# Battery_board_V4_1_-_simple_signals.net
KiCad netlist of a schematic drawn in EAGLE
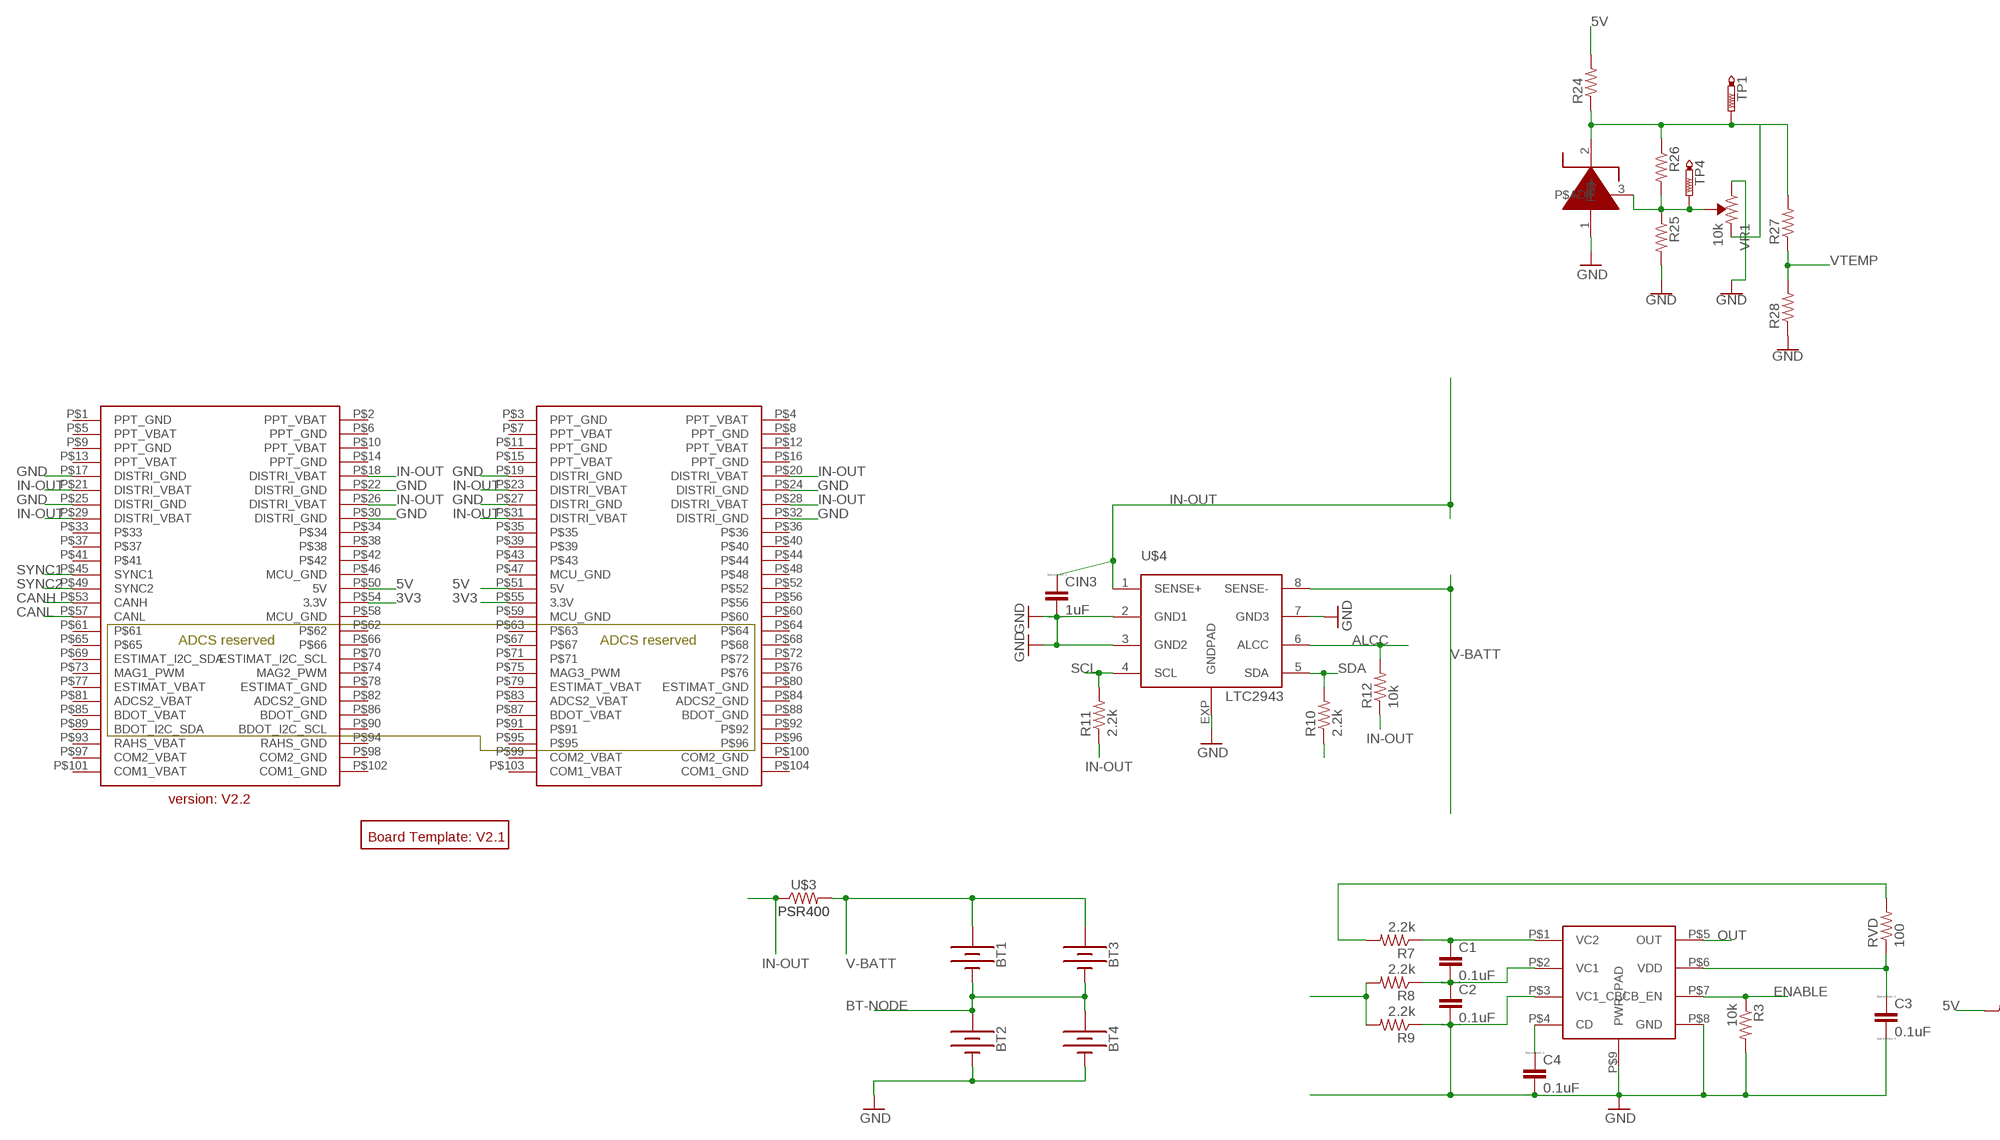
[diagram p0: schematic, sheet 1, part 1 of 2]
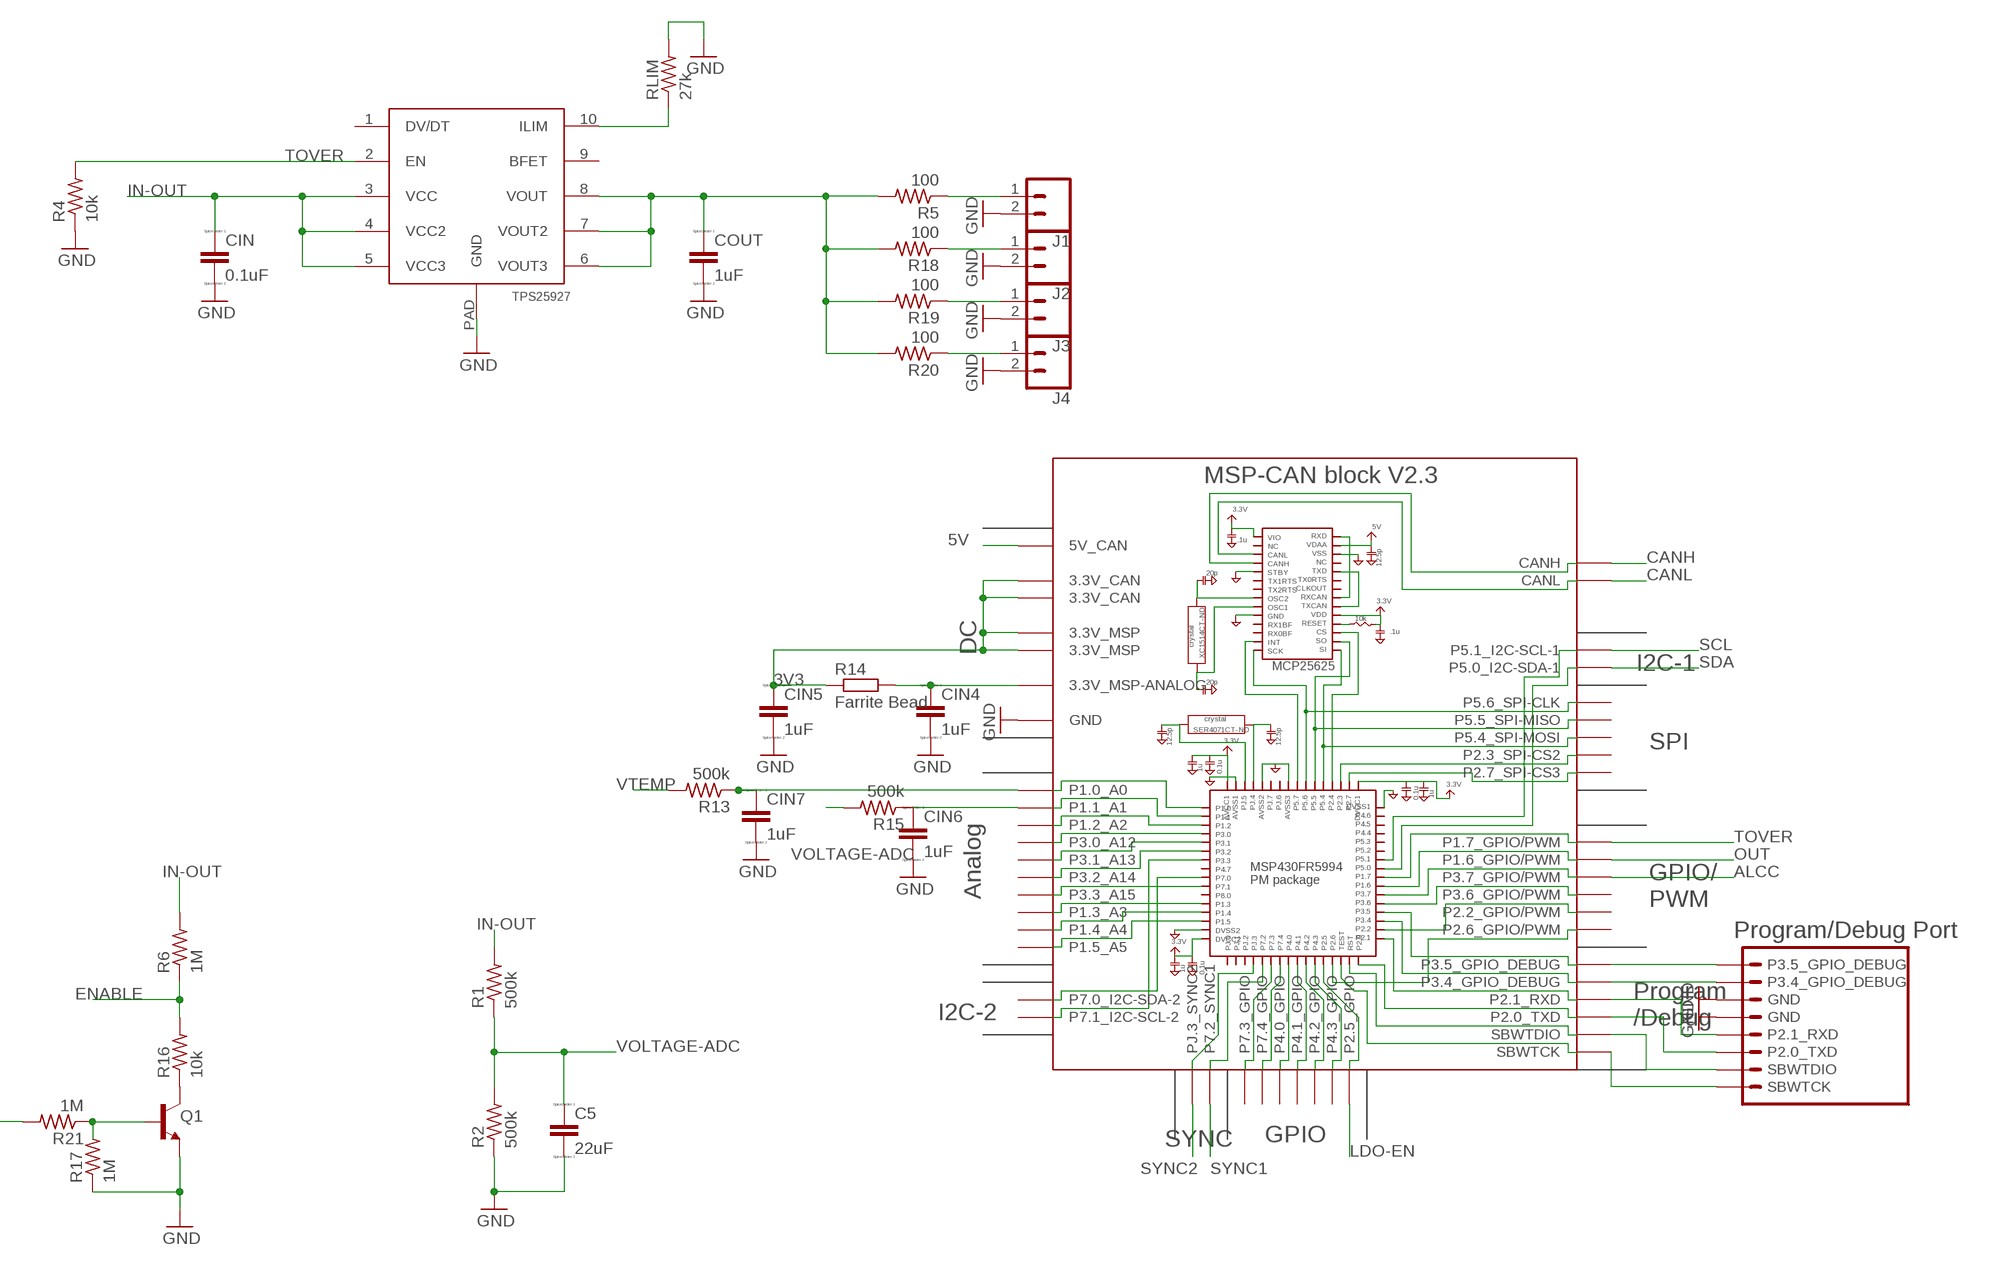
[diagram p1: schematic, sheet 1, part 2 of 2]

(export (version "E")
  (design (tool "Eeschema 10.0.6"))
  (components
    (comp (ref "BT1")
      (value "BATTERY-18650")
      (footprint "eagle-import:BATTERY_18650-HOLDER")
      (libsource (lib "eagle-import") (part "BATTERY-18650"))
    )
    (comp (ref "BT2")
      (value "BATTERY-18650")
      (footprint "eagle-import:BATTERY_18650-HOLDER")
      (libsource (lib "eagle-import") (part "BATTERY-18650"))
    )
    (comp (ref "BT3")
      (value "BATTERY-18650")
      (footprint "eagle-import:BATTERY_18650-HOLDER")
      (libsource (lib "eagle-import") (part "BATTERY-18650"))
    )
    (comp (ref "BT4")
      (value "BATTERY-18650")
      (footprint "eagle-import:BATTERY_18650-HOLDER")
      (libsource (lib "eagle-import") (part "BATTERY-18650"))
    )
    (comp (ref "C1")
      (value "0.1uF")
      (footprint "eagle-import:C0805")
      (libsource (lib "eagle-import") (part "C"))
    )
    (comp (ref "C2")
      (value "0.1uF")
      (footprint "eagle-import:C0805")
      (libsource (lib "eagle-import") (part "C"))
    )
    (comp (ref "C3")
      (value "0.1uF")
      (footprint "eagle-import:C0805")
      (libsource (lib "eagle-import") (part "C"))
    )
    (comp (ref "C4")
      (value "0.1uF")
      (footprint "eagle-import:C0805")
      (libsource (lib "eagle-import") (part "C"))
    )
    (comp (ref "C5")
      (value "22uF")
      (footprint "eagle-import:C1206")
      (libsource (lib "eagle-import") (part "CC1206"))
    )
    (comp (ref "CIN")
      (value "0.1uF")
      (footprint "eagle-import:C0805")
      (libsource (lib "eagle-import") (part "C"))
    )
    (comp (ref "CIN3")
      (value "1uF")
      (footprint "eagle-import:C0805")
      (libsource (lib "eagle-import") (part "C"))
    )
    (comp (ref "CIN4")
      (value "1uF")
      (footprint "eagle-import:C0805")
      (libsource (lib "eagle-import") (part "C"))
    )
    (comp (ref "CIN5")
      (value "1uF")
      (footprint "eagle-import:C0805")
      (libsource (lib "eagle-import") (part "C"))
    )
    (comp (ref "CIN6")
      (value "1uF")
      (footprint "eagle-import:C0805")
      (libsource (lib "eagle-import") (part "C"))
    )
    (comp (ref "CIN7")
      (value "1uF")
      (footprint "eagle-import:C0805")
      (libsource (lib "eagle-import") (part "C"))
    )
    (comp (ref "COUT")
      (value "1uF")
      (footprint "eagle-import:C0805")
      (libsource (lib "eagle-import") (part "C"))
    )
    (comp (ref "J1")
      (value "CONN_02PTH3")
      (footprint "eagle-import:1X02_LONGPADS")
      (libsource (lib "eagle-import") (part "CONN_02PTH3"))
    )
    (comp (ref "J2")
      (value "CONN_02PTH3")
      (footprint "eagle-import:1X02_LONGPADS")
      (libsource (lib "eagle-import") (part "CONN_02PTH3"))
    )
    (comp (ref "J3")
      (value "CONN_02PTH3")
      (footprint "eagle-import:1X02_LONGPADS")
      (libsource (lib "eagle-import") (part "CONN_02PTH3"))
    )
    (comp (ref "J4")
      (value "CONN_02PTH3")
      (footprint "eagle-import:1X02_LONGPADS")
      (libsource (lib "eagle-import") (part "CONN_02PTH3"))
    )
    (comp (ref "Q1")
      (value "TRANS_NPN-MMBT2222AL")
      (footprint "eagle-import:SOT23-3")
      (libsource (lib "eagle-import") (part "TRANS_NPN-MMBT2222AL"))
    )
    (comp (ref "R1")
      (value "500k")
      (footprint "eagle-import:R0805")
      (libsource (lib "eagle-import") (part "R-US_R0805"))
    )
    (comp (ref "R2")
      (value "500k")
      (footprint "eagle-import:R0805")
      (libsource (lib "eagle-import") (part "R-US_R0805"))
    )
    (comp (ref "R3")
      (value "10k")
      (footprint "eagle-import:R0805")
      (libsource (lib "eagle-import") (part "R-US_R0805"))
    )
    (comp (ref "R4")
      (value "10k")
      (footprint "eagle-import:R0805")
      (libsource (lib "eagle-import") (part "R-US_R0805"))
    )
    (comp (ref "R5")
      (value "100")
      (footprint "eagle-import:R0805")
      (libsource (lib "eagle-import") (part "R-US_R0805"))
    )
    (comp (ref "R6")
      (value "1M")
      (footprint "eagle-import:R0805")
      (libsource (lib "eagle-import") (part "R-US_R0805"))
    )
    (comp (ref "R7")
      (value "2.2k")
      (footprint "eagle-import:R0805")
      (libsource (lib "eagle-import") (part "R-US_R0805"))
    )
    (comp (ref "R8")
      (value "2.2k")
      (footprint "eagle-import:R0805")
      (libsource (lib "eagle-import") (part "R-US_R0805"))
    )
    (comp (ref "R9")
      (value "2.2k")
      (footprint "eagle-import:R0805")
      (libsource (lib "eagle-import") (part "R-US_R0805"))
    )
    (comp (ref "R10")
      (value "2.2k")
      (footprint "eagle-import:R0805")
      (libsource (lib "eagle-import") (part "R-US_R0805"))
    )
    (comp (ref "R11")
      (value "2.2k")
      (footprint "eagle-import:R0805")
      (libsource (lib "eagle-import") (part "R-US_R0805"))
    )
    (comp (ref "R12")
      (value "10k")
      (footprint "eagle-import:R0805")
      (libsource (lib "eagle-import") (part "R-US_R0805"))
    )
    (comp (ref "R13")
      (value "500k")
      (footprint "eagle-import:R0805")
      (libsource (lib "eagle-import") (part "R-US_R0805"))
    )
    (comp (ref "R14")
      (value "Farrite Bead")
      (footprint "eagle-import:R1206")
      (libsource (lib "eagle-import") (part "R-EU_R1206"))
    )
    (comp (ref "R15")
      (value "500k")
      (footprint "eagle-import:R0805")
      (libsource (lib "eagle-import") (part "R-US_R0805"))
    )
    (comp (ref "R16")
      (value "10k")
      (footprint "eagle-import:R0805")
      (libsource (lib "eagle-import") (part "R-US_R0805"))
    )
    (comp (ref "R17")
      (value "1M")
      (footprint "eagle-import:M0805")
      (libsource (lib "eagle-import") (part "R-US_M0805"))
    )
    (comp (ref "R18")
      (value "100")
      (footprint "eagle-import:R0805")
      (libsource (lib "eagle-import") (part "R-US_R0805"))
    )
    (comp (ref "R19")
      (value "100")
      (footprint "eagle-import:R0805")
      (libsource (lib "eagle-import") (part "R-US_R0805"))
    )
    (comp (ref "R20")
      (value "100")
      (footprint "eagle-import:R0805")
      (libsource (lib "eagle-import") (part "R-US_R0805"))
    )
    (comp (ref "R21")
      (value "1M")
      (footprint "eagle-import:M0805")
      (libsource (lib "eagle-import") (part "R-US_M0805"))
    )
    (comp (ref "R24")
      (value "R-US_R0805")
      (footprint "eagle-import:R0805")
      (libsource (lib "eagle-import") (part "R-US_R0805"))
    )
    (comp (ref "R25")
      (value "R-US_R0805")
      (footprint "eagle-import:R0805")
      (libsource (lib "eagle-import") (part "R-US_R0805"))
    )
    (comp (ref "R26")
      (value "R-US_R0805")
      (footprint "eagle-import:R0805")
      (libsource (lib "eagle-import") (part "R-US_R0805"))
    )
    (comp (ref "R27")
      (value "R-US_R0805")
      (footprint "eagle-import:R0805")
      (libsource (lib "eagle-import") (part "R-US_R0805"))
    )
    (comp (ref "R28")
      (value "R-US_R0805")
      (footprint "eagle-import:R0805")
      (libsource (lib "eagle-import") (part "R-US_R0805"))
    )
    (comp (ref "RLIM")
      (value "27k")
      (footprint "eagle-import:R0805")
      (libsource (lib "eagle-import") (part "R-US_R0805"))
    )
    (comp (ref "RVD")
      (value "100")
      (footprint "eagle-import:R0805")
      (libsource (lib "eagle-import") (part "R-US_R0805"))
    )
    (comp (ref "TP1")
      (value "PTR1PAD1-13Y")
      (footprint "eagle-import:P1-13Y")
      (libsource (lib "eagle-import") (part "PTR1PAD1-13Y"))
    )
    (comp (ref "TP4")
      (value "PTR1PAD1-13Y")
      (footprint "eagle-import:P1-13Y")
      (libsource (lib "eagle-import") (part "PTR1PAD1-13Y"))
    )
    (comp (ref "U$1")
      (value "MSP-CAN_BLOCK")
      (footprint "eagle-import:MSP-CAN_BLOCK")
      (libsource (lib "eagle-import") (part "MSP-CAN_BLOCK"))
    )
    (comp (ref "U$2")
      (value "PROGRAM/DEBUG_PORT")
      (footprint "eagle-import:1X08_CONNECTOR")
      (libsource (lib "eagle-import") (part "PROGRAM/DEBUG_PORT"))
    )
    (comp (ref "U$3")
      (value "PSR400")
      (footprint "eagle-import:PSR400")
      (libsource (lib "eagle-import") (part "PSR400"))
    )
    (comp (ref "U$4")
      (value "LTC2943")
      (footprint "eagle-import:DFN8(3X3)LT")
      (libsource (lib "eagle-import") (part "LTC2943"))
    )
    (comp (ref "U$5")
      (value "TPS252927")
      (footprint "eagle-import:VSON10")
      (libsource (lib "eagle-import") (part "TPS252927"))
    )
    (comp (ref "U$7")
      (value "2X26_CONNECTOR_(V2.2)")
      (footprint "eagle-import:4X26_CONNECTOR_(V2.2)")
      (libsource (lib "eagle-import") (part "2X26_CONNECTOR_(V2.2)"))
    )
    (comp (ref "U$8")
      (value "BQ29209")
      (footprint "eagle-import:VSON8")
      (libsource (lib "eagle-import") (part "BQ29209"))
    )
    (comp (ref "U$9")
      (value "BOARD_TEMPLATE_(V2.1)")
      (footprint "eagle-import:BOARD_TEMPLATE_(V2.1)")
      (libsource (lib "eagle-import") (part "BOARD_TEMPLATE_(V2.1)"))
    )
    (comp (ref "U$10")
      (value "LM135Z")
      (footprint "eagle-import:TO-92-3")
      (libsource (lib "eagle-import") (part "LM135Z"))
    )
    (comp (ref "VR1")
      (value "10k")
      (footprint "eagle-import:TRIMPOT-SMD-TC33X")
      (libsource (lib "eagle-import") (part "TRIMPOT-SMD-3MM-OPEN-1/10W-25%"))
    )
  )
  (nets
    (net (code "1") (name "/3V3") (class "Default")
      (node (ref "CIN5") (pin "1") (pinfunction "1_1") (pintype "passive"))
      (node (ref "R14") (pin "1") (pinfunction "1_1") (pintype "passive"))
      (node (ref "U$1") (pin "3.3V@CAN1") (pinfunction "3.3V_CAN_3.3V@CAN1") (pintype "bidirectional"))
      (node (ref "U$1") (pin "3.3V@CAN2") (pinfunction "3.3V_CAN_3.3V@CAN2") (pintype "bidirectional"))
      (node (ref "U$1") (pin "3.3V@MSP1") (pinfunction "3.3V_MSP_3.3V@MSP1") (pintype "bidirectional"))
      (node (ref "U$1") (pin "3.3V@MSP2") (pinfunction "3.3V_MSP_3.3V@MSP2") (pintype "bidirectional"))
      (node (ref "U$7") (pin "P$54") (pinfunction "3.3V_P$54") (pintype "bidirectional"))
      (node (ref "U$7") (pin "P$55") (pinfunction "3.3V_P$55") (pintype "bidirectional"))
    )
    (net (code "2") (name "/5V") (class "Default")
      (node (ref "R21") (pin "2") (pinfunction "2_2") (pintype "passive"))
      (node (ref "R24") (pin "2") (pinfunction "2_2") (pintype "passive"))
      (node (ref "U$1") (pin "5V") (pinfunction "5V_CAN_5V") (pintype "bidirectional"))
      (node (ref "U$7") (pin "P$50") (pinfunction "5V_P$50") (pintype "bidirectional"))
      (node (ref "U$7") (pin "P$51") (pinfunction "5V_P$51") (pintype "bidirectional"))
    )
    (net (code "3") (name "/ALCC") (class "Default")
      (node (ref "R12") (pin "2") (pinfunction "2_2") (pintype "passive"))
      (node (ref "U$1") (pin "P3.7_GPIO/PWM") (pinfunction "P3.7_GPIO/PWM_P3.7_GPIO/PWM") (pintype "bidirectional"))
      (node (ref "U$4") (pin "6") (pinfunction "ALCC_6") (pintype "bidirectional"))
    )
    (net (code "4") (name "/BT-NODE") (class "Default")
      (node (ref "BT1") (pin "GND@1") (pinfunction "-_GND@1") (pintype "power_in"))
      (node (ref "BT2") (pin "PWR@1") (pinfunction "+_PWR@1") (pintype "power_in"))
      (node (ref "BT3") (pin "GND@1") (pinfunction "-_GND@1") (pintype "power_in"))
      (node (ref "BT4") (pin "PWR@1") (pinfunction "+_PWR@1") (pintype "power_in"))
      (node (ref "R8") (pin "2") (pinfunction "2_2") (pintype "passive"))
      (node (ref "R9") (pin "2") (pinfunction "2_2") (pintype "passive"))
    )
    (net (code "5") (name "/CANH") (class "Default")
      (node (ref "U$1") (pin "CANH") (pinfunction "CANH_CANH") (pintype "bidirectional"))
      (node (ref "U$7") (pin "P$53") (pinfunction "CANH_P$53") (pintype "bidirectional"))
    )
    (net (code "6") (name "/CANL") (class "Default")
      (node (ref "U$1") (pin "CANL") (pinfunction "CANL_CANL") (pintype "bidirectional"))
      (node (ref "U$7") (pin "P$57") (pinfunction "CANL_P$57") (pintype "bidirectional"))
    )
    (net (code "7") (name "/ENABLE") (class "Default")
      (node (ref "R16") (pin "2") (pinfunction "2_2") (pintype "passive"))
      (node (ref "R3") (pin "1") (pinfunction "1_1") (pintype "passive"))
      (node (ref "R6") (pin "1") (pinfunction "1_1") (pintype "passive"))
      (node (ref "U$8") (pin "P$7") (pinfunction "CB_EN_P$7") (pintype "bidirectional"))
    )
    (net (code "8") (name "/IN-OUT") (class "Default")
      (node (ref "CIN") (pin "1") (pinfunction "1_1") (pintype "passive"))
      (node (ref "CIN3") (pin "1") (pinfunction "1_1") (pintype "passive"))
      (node (ref "R1") (pin "2") (pinfunction "2_2") (pintype "passive"))
      (node (ref "R10") (pin "1") (pinfunction "1_1") (pintype "passive"))
      (node (ref "R11") (pin "1") (pinfunction "1_1") (pintype "passive"))
      (node (ref "R12") (pin "1") (pinfunction "1_1") (pintype "passive"))
      (node (ref "R6") (pin "2") (pinfunction "2_2") (pintype "passive"))
      (node (ref "U$3") (pin "P$1") (pinfunction "1_P$1") (pintype "passive"))
      (node (ref "U$4") (pin "1") (pinfunction "SENSE+_1") (pintype "bidirectional"))
      (node (ref "U$5") (pin "3") (pinfunction "VCC_3") (pintype "bidirectional"))
      (node (ref "U$5") (pin "4") (pinfunction "VCC2_4") (pintype "bidirectional"))
      (node (ref "U$5") (pin "5") (pinfunction "VCC3_5") (pintype "bidirectional"))
      (node (ref "U$7") (pin "P$18") (pinfunction "DISTRI_VBAT_P$18") (pintype "bidirectional"))
      (node (ref "U$7") (pin "P$20") (pinfunction "DISTRI_VBAT_P$20") (pintype "bidirectional"))
      (node (ref "U$7") (pin "P$21") (pinfunction "DISTRI_VBAT_P$21") (pintype "bidirectional"))
      (node (ref "U$7") (pin "P$23") (pinfunction "DISTRI_VBAT_P$23") (pintype "bidirectional"))
      (node (ref "U$7") (pin "P$26") (pinfunction "DISTRI_VBAT_P$26") (pintype "bidirectional"))
      (node (ref "U$7") (pin "P$28") (pinfunction "DISTRI_VBAT_P$28") (pintype "bidirectional"))
      (node (ref "U$7") (pin "P$29") (pinfunction "DISTRI_VBAT_P$29") (pintype "bidirectional"))
      (node (ref "U$7") (pin "P$31") (pinfunction "DISTRI_VBAT_P$31") (pintype "bidirectional"))
    )
    (net (code "9") (name "/LDO-EN") (class "Default")
      (node (ref "U$1") (pin "P2.5_GPIO") (pinfunction "P2.5_GPIO_P2.5_GPIO") (pintype "bidirectional"))
    )
    (net (code "10") (name "/OUT") (class "Default")
      (node (ref "U$1") (pin "P1.6_GPIO/PWM") (pinfunction "P1.6_GPIO/PWM_P1.6_GPIO/PWM") (pintype "bidirectional"))
      (node (ref "U$8") (pin "P$5") (pinfunction "OUT_P$5") (pintype "bidirectional"))
    )
    (net (code "11") (name "/SCL") (class "Default")
      (node (ref "R11") (pin "2") (pinfunction "2_2") (pintype "passive"))
      (node (ref "U$1") (pin "P5.1_I2C-SCL-1") (pinfunction "P5.1_I2C-SCL-1_P5.1_I2C-SCL-1") (pintype "bidirectional"))
      (node (ref "U$4") (pin "4") (pinfunction "SCL_4") (pintype "bidirectional"))
    )
    (net (code "12") (name "/SDA") (class "Default")
      (node (ref "R10") (pin "2") (pinfunction "2_2") (pintype "passive"))
      (node (ref "U$1") (pin "P5.0_I2C-SDA-1") (pinfunction "P5.0_I2C-SDA-1_P5.0_I2C-SDA-1") (pintype "bidirectional"))
      (node (ref "U$4") (pin "5") (pinfunction "SDA_5") (pintype "bidirectional"))
    )
    (net (code "13") (name "/SYNC1") (class "Default")
      (node (ref "U$1") (pin "P7.2_SYNC1") (pinfunction "P7.2_SYNC1_P7.2_SYNC1") (pintype "bidirectional"))
      (node (ref "U$7") (pin "P$45") (pinfunction "SYNC1_P$45") (pintype "bidirectional"))
    )
    (net (code "14") (name "/SYNC2") (class "Default")
      (node (ref "U$1") (pin "PJ.3_SYNC2") (pinfunction "PJ.3_SYNC2_PJ.3_SYNC2") (pintype "bidirectional"))
      (node (ref "U$7") (pin "P$49") (pinfunction "SYNC2_P$49") (pintype "bidirectional"))
    )
    (net (code "15") (name "/TOVER") (class "Default")
      (node (ref "R4") (pin "2") (pinfunction "2_2") (pintype "passive"))
      (node (ref "U$1") (pin "P1.7_GPIO/PWM") (pinfunction "P1.7_GPIO/PWM_P1.7_GPIO/PWM") (pintype "bidirectional"))
      (node (ref "U$5") (pin "2") (pinfunction "EN_2") (pintype "bidirectional"))
    )
    (net (code "16") (name "/V-BATT") (class "Default")
      (node (ref "BT1") (pin "PWR@1") (pinfunction "+_PWR@1") (pintype "power_in"))
      (node (ref "BT3") (pin "PWR@1") (pinfunction "+_PWR@1") (pintype "power_in"))
      (node (ref "R7") (pin "2") (pinfunction "2_2") (pintype "passive"))
      (node (ref "RVD") (pin "2") (pinfunction "2_2") (pintype "passive"))
      (node (ref "U$3") (pin "P$2") (pinfunction "2_P$2") (pintype "passive"))
      (node (ref "U$4") (pin "8") (pinfunction "SENSE-_8") (pintype "bidirectional"))
    )
    (net (code "17") (name "/VOLTAGE-ADC") (class "Default")
      (node (ref "C5") (pin "1") (pinfunction "1_1") (pintype "passive"))
      (node (ref "R1") (pin "1") (pinfunction "1_1") (pintype "passive"))
      (node (ref "R15") (pin "2") (pinfunction "2_2") (pintype "passive"))
      (node (ref "R2") (pin "2") (pinfunction "2_2") (pintype "passive"))
    )
    (net (code "18") (name "/VTEMP") (class "Default")
      (node (ref "R13") (pin "2") (pinfunction "2_2") (pintype "passive"))
      (node (ref "R27") (pin "1") (pinfunction "1_1") (pintype "passive"))
      (node (ref "R28") (pin "2") (pinfunction "2_2") (pintype "passive"))
    )
    (net (code "19") (name "GND") (class "Default")
      (node (ref "BT2") (pin "GND@1") (pinfunction "-_GND@1") (pintype "power_in"))
      (node (ref "BT4") (pin "GND@1") (pinfunction "-_GND@1") (pintype "power_in"))
      (node (ref "C2") (pin "2") (pinfunction "2_2") (pintype "passive"))
      (node (ref "C3") (pin "2") (pinfunction "2_2") (pintype "passive"))
      (node (ref "C4") (pin "2") (pinfunction "2_2") (pintype "passive"))
      (node (ref "C5") (pin "2") (pinfunction "2_2") (pintype "passive"))
      (node (ref "CIN") (pin "2") (pinfunction "2_2") (pintype "passive"))
      (node (ref "CIN3") (pin "2") (pinfunction "2_2") (pintype "passive"))
      (node (ref "CIN4") (pin "2") (pinfunction "2_2") (pintype "passive"))
      (node (ref "CIN5") (pin "2") (pinfunction "2_2") (pintype "passive"))
      (node (ref "CIN6") (pin "2") (pinfunction "2_2") (pintype "passive"))
      (node (ref "CIN7") (pin "2") (pinfunction "2_2") (pintype "passive"))
      (node (ref "COUT") (pin "2") (pinfunction "2_2") (pintype "passive"))
      (node (ref "J1") (pin "2") (pinfunction "2_2") (pintype "passive"))
      (node (ref "J2") (pin "2") (pinfunction "2_2") (pintype "passive"))
      (node (ref "J3") (pin "2") (pinfunction "2_2") (pintype "passive"))
      (node (ref "J4") (pin "2") (pinfunction "2_2") (pintype "passive"))
      (node (ref "Q1") (pin "2") (pinfunction "E_2") (pintype "passive"))
      (node (ref "R17") (pin "1") (pinfunction "1_1") (pintype "passive"))
      (node (ref "R2") (pin "1") (pinfunction "1_1") (pintype "passive"))
      (node (ref "R25") (pin "2") (pinfunction "2_2") (pintype "passive"))
      (node (ref "R28") (pin "1") (pinfunction "1_1") (pintype "passive"))
      (node (ref "R3") (pin "2") (pinfunction "2_2") (pintype "passive"))
      (node (ref "R4") (pin "1") (pinfunction "1_1") (pintype "passive"))
      (node (ref "R9") (pin "1") (pinfunction "1_1") (pintype "passive"))
      (node (ref "RLIM") (pin "2") (pinfunction "2_2") (pintype "passive"))
      (node (ref "U$1") (pin "GND@1") (pinfunction "GND_GND@1") (pintype "bidirectional"))
      (node (ref "U$1") (pin "GND@10") (pinfunction "GND_GND@10") (pintype "bidirectional"))
      (node (ref "U$1") (pin "GND@11") (pinfunction "GND_GND@11") (pintype "bidirectional"))
      (node (ref "U$1") (pin "GND@12") (pinfunction "GND_GND@12") (pintype "bidirectional"))
      (node (ref "U$1") (pin "GND@13") (pinfunction "GND_GND@13") (pintype "bidirectional"))
      (node (ref "U$1") (pin "GND@14") (pinfunction "GND_GND@14") (pintype "bidirectional"))
      (node (ref "U$1") (pin "GND@15") (pinfunction "GND_GND@15") (pintype "bidirectional"))
      (node (ref "U$1") (pin "GND@16") (pinfunction "GND_GND@16") (pintype "bidirectional"))
      (node (ref "U$1") (pin "GND@17") (pinfunction "GND_GND@17") (pintype "bidirectional"))
      (node (ref "U$1") (pin "GND@2") (pinfunction "GND_GND@2") (pintype "bidirectional"))
      (node (ref "U$1") (pin "GND@26") (pinfunction "GND_GND@26") (pintype "bidirectional"))
      (node (ref "U$1") (pin "GND@3") (pinfunction "GND_GND@3") (pintype "bidirectional"))
      (node (ref "U$1") (pin "GND@4") (pinfunction "GND_GND@4") (pintype "bidirectional"))
      (node (ref "U$1") (pin "GND@5") (pinfunction "GND_GND@5") (pintype "bidirectional"))
      (node (ref "U$1") (pin "GND@7") (pinfunction "GND_GND@7") (pintype "bidirectional"))
      (node (ref "U$1") (pin "GND@8") (pinfunction "GND_GND@8") (pintype "bidirectional"))
      (node (ref "U$1") (pin "GND@9") (pinfunction "GND_GND@9") (pintype "bidirectional"))
      (node (ref "U$10") (pin "1") (pinfunction "P$-_1") (pintype "bidirectional"))
      (node (ref "U$2") (pin "5") (pinfunction "GND_5") (pintype "bidirectional"))
      (node (ref "U$2") (pin "6") (pinfunction "GND_6") (pintype "bidirectional"))
      (node (ref "U$4") (pin "2") (pinfunction "GND1_2") (pintype "bidirectional"))
      (node (ref "U$4") (pin "3") (pinfunction "GND2_3") (pintype "bidirectional"))
      (node (ref "U$4") (pin "7") (pinfunction "GND3_7") (pintype "bidirectional"))
      (node (ref "U$4") (pin "EXP") (pinfunction "GNDPAD_EXP") (pintype "bidirectional"))
      (node (ref "U$5") (pin "PAD") (pinfunction "GND_PAD") (pintype "bidirectional"))
      (node (ref "U$7") (pin "P$17") (pinfunction "DISTRI_GND_P$17") (pintype "bidirectional"))
      (node (ref "U$7") (pin "P$19") (pinfunction "DISTRI_GND_P$19") (pintype "bidirectional"))
      (node (ref "U$7") (pin "P$22") (pinfunction "DISTRI_GND_P$22") (pintype "bidirectional"))
      (node (ref "U$7") (pin "P$24") (pinfunction "DISTRI_GND_P$24") (pintype "bidirectional"))
      (node (ref "U$7") (pin "P$25") (pinfunction "DISTRI_GND_P$25") (pintype "bidirectional"))
      (node (ref "U$7") (pin "P$27") (pinfunction "DISTRI_GND_P$27") (pintype "bidirectional"))
      (node (ref "U$7") (pin "P$30") (pinfunction "DISTRI_GND_P$30") (pintype "bidirectional"))
      (node (ref "U$7") (pin "P$32") (pinfunction "DISTRI_GND_P$32") (pintype "bidirectional"))
      (node (ref "U$8") (pin "P$3") (pinfunction "VC1_CB_P$3") (pintype "bidirectional"))
      (node (ref "U$8") (pin "P$8") (pinfunction "GND_P$8") (pintype "bidirectional"))
      (node (ref "U$8") (pin "P$9") (pinfunction "PWR_PAD_P$9") (pintype "bidirectional"))
      (node (ref "VR1") (pin "1") (pinfunction "CW_1") (pintype "passive"))
    )
    (net (code "20") (name "Net-(CIN6-Pad1)") (class "Default")
      (node (ref "CIN6") (pin "1") (pinfunction "1_1") (pintype "passive"))
      (node (ref "R15") (pin "1") (pinfunction "1_1") (pintype "passive"))
      (node (ref "U$1") (pin "P1.1_A1") (pinfunction "P1.1_A1_P1.1_A1") (pintype "bidirectional"))
    )
    (net (code "21") (name "Net-(CIN7-Pad1)") (class "Default")
      (node (ref "CIN7") (pin "1") (pinfunction "1_1") (pintype "passive"))
      (node (ref "R13") (pin "1") (pinfunction "1_1") (pintype "passive"))
      (node (ref "U$1") (pin "P1.0_A0") (pinfunction "P1.0_A0_P1.0_A0") (pintype "bidirectional"))
    )
    (net (code "22") (name "Net-(J1-Pad1)") (class "Default")
      (node (ref "J1") (pin "1") (pinfunction "1_1") (pintype "passive"))
      (node (ref "R5") (pin "1") (pinfunction "1_1") (pintype "passive"))
    )
    (net (code "23") (name "Net-(J2-Pad1)") (class "Default")
      (node (ref "J2") (pin "1") (pinfunction "1_1") (pintype "passive"))
      (node (ref "R18") (pin "1") (pinfunction "1_1") (pintype "passive"))
    )
    (net (code "24") (name "Net-(J3-Pad1)") (class "Default")
      (node (ref "J3") (pin "1") (pinfunction "1_1") (pintype "passive"))
      (node (ref "R19") (pin "1") (pinfunction "1_1") (pintype "passive"))
    )
    (net (code "25") (name "Net-(J4-Pad1)") (class "Default")
      (node (ref "J4") (pin "1") (pinfunction "1_1") (pintype "passive"))
      (node (ref "R20") (pin "1") (pinfunction "1_1") (pintype "passive"))
    )
    (net (code "26") (name "Net-(Q1-B)") (class "Default")
      (node (ref "Q1") (pin "1") (pinfunction "B_1") (pintype "passive"))
      (node (ref "R17") (pin "2") (pinfunction "2_2") (pintype "passive"))
      (node (ref "R21") (pin "1") (pinfunction "1_1") (pintype "passive"))
    )
    (net (code "27") (name "Net-(Q1-C)") (class "Default")
      (node (ref "Q1") (pin "3") (pinfunction "C_3") (pintype "passive"))
      (node (ref "R16") (pin "1") (pinfunction "1_1") (pintype "passive"))
    )
    (net (code "28") (name "Net-(U$1-3.3V_MSP-ANALOG)") (class "Default")
      (node (ref "CIN4") (pin "1") (pinfunction "1_1") (pintype "passive"))
      (node (ref "R14") (pin "2") (pinfunction "2_2") (pintype "passive"))
      (node (ref "U$1") (pin "3.3V_ANALOG@MSP2") (pinfunction "3.3V_MSP-ANALOG_3.3V_ANALOG@MSP2") (pintype "bidirectional"))
    )
    (net (code "29") (name "Net-(U$1-PadSBWTCK)") (class "Default")
      (node (ref "U$1") (pin "SBWTCK") (pinfunction "SBWTCK_SBWTCK") (pintype "bidirectional"))
      (node (ref "U$2") (pin "SBWTCK") (pinfunction "SBWTCK_SBWTCK") (pintype "bidirectional"))
    )
    (net (code "30") (name "Net-(U$2-P2.0_TXD)") (class "Default")
      (node (ref "U$1") (pin "P2.0_TXD") (pinfunction "P2.0_TXD_P2.0_TXD") (pintype "bidirectional"))
      (node (ref "U$2") (pin "3") (pinfunction "P2.0_TXD_3") (pintype "bidirectional"))
    )
    (net (code "31") (name "Net-(U$2-P2.1_RXD)") (class "Default")
      (node (ref "U$1") (pin "P2.1_RXD") (pinfunction "P2.1_RXD_P2.1_RXD") (pintype "bidirectional"))
      (node (ref "U$2") (pin "4") (pinfunction "P2.1_RXD_4") (pintype "bidirectional"))
    )
    (net (code "32") (name "Net-(U$2-P3.4_GPIO_DEBUG)") (class "Default")
      (node (ref "U$1") (pin "P3.4_GPIO_DEBUG") (pinfunction "P3.4_GPIO_DEBUG_P3.4_GPIO_DEBUG") (pintype "bidirectional"))
      (node (ref "U$2") (pin "7") (pinfunction "P3.4_GPIO_DEBUG_7") (pintype "bidirectional"))
    )
    (net (code "33") (name "Net-(U$2-P3.5_GPIO_DEBUG)") (class "Default")
      (node (ref "U$1") (pin "P3.5_GPIO_DEBUG") (pinfunction "P3.5_GPIO_DEBUG_P3.5_GPIO_DEBUG") (pintype "bidirectional"))
      (node (ref "U$2") (pin "8") (pinfunction "P3.5_GPIO_DEBUG_8") (pintype "bidirectional"))
    )
    (net (code "34") (name "Net-(U$2-SBWTDIO)") (class "Default")
      (node (ref "U$1") (pin "SBWTDIO") (pinfunction "SBWTDIO_SBWTDIO") (pintype "bidirectional"))
      (node (ref "U$2") (pin "2") (pinfunction "SBWTDIO_2") (pintype "bidirectional"))
    )
    (net (code "35") (name "Net-(U$5-ILIM)") (class "Default")
      (node (ref "RLIM") (pin "1") (pinfunction "1_1") (pintype "passive"))
      (node (ref "U$5") (pin "10") (pinfunction "ILIM_10") (pintype "bidirectional"))
    )
    (net (code "36") (name "Net-(U$5-VOUT)") (class "Default")
      (node (ref "COUT") (pin "1") (pinfunction "1_1") (pintype "passive"))
      (node (ref "R18") (pin "2") (pinfunction "2_2") (pintype "passive"))
      (node (ref "R19") (pin "2") (pinfunction "2_2") (pintype "passive"))
      (node (ref "R20") (pin "2") (pinfunction "2_2") (pintype "passive"))
      (node (ref "R5") (pin "2") (pinfunction "2_2") (pintype "passive"))
      (node (ref "U$5") (pin "6") (pinfunction "VOUT3_6") (pintype "bidirectional"))
      (node (ref "U$5") (pin "7") (pinfunction "VOUT2_7") (pintype "bidirectional"))
      (node (ref "U$5") (pin "8") (pinfunction "VOUT_8") (pintype "bidirectional"))
    )
    (net (code "37") (name "Net-(U$8-CD)") (class "Default")
      (node (ref "C4") (pin "1") (pinfunction "1_1") (pintype "passive"))
      (node (ref "U$8") (pin "P$4") (pinfunction "CD_P$4") (pintype "bidirectional"))
    )
    (net (code "38") (name "Net-(U$8-VC1)") (class "Default")
      (node (ref "C1") (pin "2") (pinfunction "2_2") (pintype "passive"))
      (node (ref "C2") (pin "1") (pinfunction "1_1") (pintype "passive"))
      (node (ref "R8") (pin "1") (pinfunction "1_1") (pintype "passive"))
      (node (ref "U$8") (pin "P$2") (pinfunction "VC1_P$2") (pintype "bidirectional"))
    )
    (net (code "39") (name "Net-(U$8-VC2)") (class "Default")
      (node (ref "C1") (pin "1") (pinfunction "1_1") (pintype "passive"))
      (node (ref "R7") (pin "1") (pinfunction "1_1") (pintype "passive"))
      (node (ref "U$8") (pin "P$1") (pinfunction "VC2_P$1") (pintype "bidirectional"))
    )
    (net (code "40") (name "Net-(U$8-VDD)") (class "Default")
      (node (ref "C3") (pin "1") (pinfunction "1_1") (pintype "passive"))
      (node (ref "RVD") (pin "1") (pinfunction "1_1") (pintype "passive"))
      (node (ref "U$8") (pin "P$6") (pinfunction "VDD_P$6") (pintype "bidirectional"))
    )
    (net (code "41") (name "Net-(U$10-P$+)") (class "Default")
      (node (ref "R24") (pin "1") (pinfunction "1_1") (pintype "passive"))
      (node (ref "R26") (pin "1") (pinfunction "1_1") (pintype "passive"))
      (node (ref "R27") (pin "2") (pinfunction "2_2") (pintype "passive"))
      (node (ref "TP1") (pin "TP") (pinfunction "TP_TP") (pintype "input"))
      (node (ref "U$10") (pin "2") (pinfunction "P$+_2") (pintype "bidirectional"))
      (node (ref "VR1") (pin "3") (pinfunction "CCW_3") (pintype "passive"))
    )
    (net (code "42") (name "Net-(U$10-P$ADJ)") (class "Default")
      (node (ref "R25") (pin "1") (pinfunction "1_1") (pintype "passive"))
      (node (ref "R26") (pin "2") (pinfunction "2_2") (pintype "passive"))
      (node (ref "TP4") (pin "TP") (pinfunction "TP_TP") (pintype "input"))
      (node (ref "U$10") (pin "3") (pinfunction "P$ADJ_3") (pintype "bidirectional"))
      (node (ref "VR1") (pin "2") (pinfunction "WIPER_2") (pintype "passive"))
    )
    (net (code "43") (name "unconnected-(U$1-P2.3_SPI-CS2-PadP2.4_SPI-CS2)") (class "Default")
      (node (ref "U$1") (pin "P2.4_SPI-CS2") (pinfunction "P2.3_SPI-CS2_P2.4_SPI-CS2") (pintype "bidirectional"))
    )
    (net (code "44") (name "unconnected-(U$1-PadP1.2_A2)") (class "Default")
      (node (ref "U$1") (pin "P1.2_A2") (pinfunction "P1.2_A2_P1.2_A2") (pintype "bidirectional"))
    )
    (net (code "45") (name "unconnected-(U$1-PadP1.3_A3)") (class "Default")
      (node (ref "U$1") (pin "P1.3_A3") (pinfunction "P1.3_A3_P1.3_A3") (pintype "bidirectional"))
    )
    (net (code "46") (name "unconnected-(U$1-PadP1.4_A4)") (class "Default")
      (node (ref "U$1") (pin "P1.4_A4") (pinfunction "P1.4_A4_P1.4_A4") (pintype "bidirectional"))
    )
    (net (code "47") (name "unconnected-(U$1-PadP1.5_A5)") (class "Default")
      (node (ref "U$1") (pin "P1.5_A5") (pinfunction "P1.5_A5_P1.5_A5") (pintype "bidirectional"))
    )
    (net (code "48") (name "unconnected-(U$1-PadP2.2_GPIO{slash}PWM)") (class "Default")
      (node (ref "U$1") (pin "P2.2_GPIO/PWM") (pinfunction "P2.2_GPIO/PWM_P2.2_GPIO/PWM") (pintype "bidirectional"))
    )
    (net (code "49") (name "unconnected-(U$1-PadP2.6_GPIO{slash}PWM)") (class "Default")
      (node (ref "U$1") (pin "P2.6_GPIO/PWM") (pinfunction "P2.6_GPIO/PWM_P2.6_GPIO/PWM") (pintype "bidirectional"))
    )
    (net (code "50") (name "unconnected-(U$1-PadP2.7_SPI-CS3)") (class "Default")
      (node (ref "U$1") (pin "P2.7_SPI-CS3") (pinfunction "P2.7_SPI-CS3_P2.7_SPI-CS3") (pintype "bidirectional"))
    )
    (net (code "51") (name "unconnected-(U$1-PadP3.0_A12)") (class "Default")
      (node (ref "U$1") (pin "P3.0_A12") (pinfunction "P3.0_A12_P3.0_A12") (pintype "bidirectional"))
    )
    (net (code "52") (name "unconnected-(U$1-PadP3.1_A13)") (class "Default")
      (node (ref "U$1") (pin "P3.1_A13") (pinfunction "P3.1_A13_P3.1_A13") (pintype "bidirectional"))
    )
    (net (code "53") (name "unconnected-(U$1-PadP3.2_A14)") (class "Default")
      (node (ref "U$1") (pin "P3.2_A14") (pinfunction "P3.2_A14_P3.2_A14") (pintype "bidirectional"))
    )
    (net (code "54") (name "unconnected-(U$1-PadP3.3_A15)") (class "Default")
      (node (ref "U$1") (pin "P3.3_A15") (pinfunction "P3.3_A15_P3.3_A15") (pintype "bidirectional"))
    )
    (net (code "55") (name "unconnected-(U$1-PadP3.6_GPIO{slash}PWM)") (class "Default")
      (node (ref "U$1") (pin "P3.6_GPIO/PWM") (pinfunction "P3.6_GPIO/PWM_P3.6_GPIO/PWM") (pintype "bidirectional"))
    )
    (net (code "56") (name "unconnected-(U$1-PadP4.0_GPIO)") (class "Default")
      (node (ref "U$1") (pin "P4.0_GPIO") (pinfunction "P4.0_GPIO_P4.0_GPIO") (pintype "bidirectional"))
    )
    (net (code "57") (name "unconnected-(U$1-PadP4.1_GPIO)") (class "Default")
      (node (ref "U$1") (pin "P4.1_GPIO") (pinfunction "P4.1_GPIO_P4.1_GPIO") (pintype "bidirectional"))
    )
    (net (code "58") (name "unconnected-(U$1-PadP4.2_GPIO)") (class "Default")
      (node (ref "U$1") (pin "P4.2_GPIO") (pinfunction "P4.2_GPIO_P4.2_GPIO") (pintype "bidirectional"))
    )
    (net (code "59") (name "unconnected-(U$1-PadP4.3_GPIO)") (class "Default")
      (node (ref "U$1") (pin "P4.3_GPIO") (pinfunction "P4.3_GPIO_P4.3_GPIO") (pintype "bidirectional"))
    )
    (net (code "60") (name "unconnected-(U$1-PadP5.4_SPI-MOSI)") (class "Default")
      (node (ref "U$1") (pin "P5.4_SPI-MOSI") (pinfunction "P5.4_SPI-MOSI_P5.4_SPI-MOSI") (pintype "bidirectional"))
    )
    (net (code "61") (name "unconnected-(U$1-PadP5.5_SPI-MISO)") (class "Default")
      (node (ref "U$1") (pin "P5.5_SPI-MISO") (pinfunction "P5.5_SPI-MISO_P5.5_SPI-MISO") (pintype "bidirectional"))
    )
    (net (code "62") (name "unconnected-(U$1-PadP5.6_SPI-CLK)") (class "Default")
      (node (ref "U$1") (pin "P5.6_SPI-CLK") (pinfunction "P5.6_SPI-CLK_P5.6_SPI-CLK") (pintype "bidirectional"))
    )
    (net (code "63") (name "unconnected-(U$1-PadP7.0_I2C-SDA-2)") (class "Default")
      (node (ref "U$1") (pin "P7.0_I2C-SDA-2") (pinfunction "P7.0_I2C-SDA-2_P7.0_I2C-SDA-2") (pintype "bidirectional"))
    )
    (net (code "64") (name "unconnected-(U$1-PadP7.1_I2C-SCL-2)") (class "Default")
      (node (ref "U$1") (pin "P7.1_I2C-SCL-2") (pinfunction "P7.1_I2C-SCL-2_P7.1_I2C-SCL-2") (pintype "bidirectional"))
    )
    (net (code "65") (name "unconnected-(U$1-PadP7.3_GPIO)") (class "Default")
      (node (ref "U$1") (pin "P7.3_GPIO") (pinfunction "P7.3_GPIO_P7.3_GPIO") (pintype "bidirectional"))
    )
    (net (code "66") (name "unconnected-(U$1-PadP7.4_GPIO)") (class "Default")
      (node (ref "U$1") (pin "P7.4_GPIO") (pinfunction "P7.4_GPIO_P7.4_GPIO") (pintype "bidirectional"))
    )
    (net (code "67") (name "unconnected-(U$5-BFET-Pad9)") (class "Default")
      (node (ref "U$5") (pin "9") (pinfunction "BFET_9") (pintype "bidirectional"))
    )
    (net (code "68") (name "unconnected-(U$5-DV{slash}DT-Pad1)") (class "Default")
      (node (ref "U$5") (pin "1") (pinfunction "DV/DT_1") (pintype "bidirectional"))
    )
    (net (code "69") (name "unconnected-(U$7-ADCS2_GND-PadP$82)") (class "Default")
      (node (ref "U$7") (pin "P$82") (pinfunction "ADCS2_GND_P$82") (pintype "bidirectional"))
    )
    (net (code "70") (name "unconnected-(U$7-ADCS2_GND-PadP$84)") (class "Default")
      (node (ref "U$7") (pin "P$84") (pinfunction "ADCS2_GND_P$84") (pintype "bidirectional"))
    )
    (net (code "71") (name "unconnected-(U$7-ADCS2_VBAT-PadP$81)") (class "Default")
      (node (ref "U$7") (pin "P$81") (pinfunction "ADCS2_VBAT_P$81") (pintype "bidirectional"))
    )
    (net (code "72") (name "unconnected-(U$7-ADCS2_VBAT-PadP$83)") (class "Default")
      (node (ref "U$7") (pin "P$83") (pinfunction "ADCS2_VBAT_P$83") (pintype "bidirectional"))
    )
    (net (code "73") (name "unconnected-(U$7-BDOT_GND-PadP$86)") (class "Default")
      (node (ref "U$7") (pin "P$86") (pinfunction "BDOT_GND_P$86") (pintype "bidirectional"))
    )
    (net (code "74") (name "unconnected-(U$7-BDOT_GND-PadP$88)") (class "Default")
      (node (ref "U$7") (pin "P$88") (pinfunction "BDOT_GND_P$88") (pintype "bidirectional"))
    )
    (net (code "75") (name "unconnected-(U$7-BDOT_I2C_SCL-PadP$90)") (class "Default")
      (node (ref "U$7") (pin "P$90") (pinfunction "BDOT_I2C_SCL_P$90") (pintype "bidirectional"))
    )
    (net (code "76") (name "unconnected-(U$7-BDOT_I2C_SDA-PadP$89)") (class "Default")
      (node (ref "U$7") (pin "P$89") (pinfunction "BDOT_I2C_SDA_P$89") (pintype "bidirectional"))
    )
    (net (code "77") (name "unconnected-(U$7-BDOT_VBAT-PadP$85)") (class "Default")
      (node (ref "U$7") (pin "P$85") (pinfunction "BDOT_VBAT_P$85") (pintype "bidirectional"))
    )
    (net (code "78") (name "unconnected-(U$7-BDOT_VBAT-PadP$87)") (class "Default")
      (node (ref "U$7") (pin "P$87") (pinfunction "BDOT_VBAT_P$87") (pintype "bidirectional"))
    )
    (net (code "79") (name "unconnected-(U$7-COM1_GND-PadP$102)") (class "Default")
      (node (ref "U$7") (pin "P$102") (pinfunction "COM1_GND_P$102") (pintype "bidirectional"))
    )
    (net (code "80") (name "unconnected-(U$7-COM1_GND-PadP$104)") (class "Default")
      (node (ref "U$7") (pin "P$104") (pinfunction "COM1_GND_P$104") (pintype "bidirectional"))
    )
    (net (code "81") (name "unconnected-(U$7-COM1_VBAT-PadP$101)") (class "Default")
      (node (ref "U$7") (pin "P$101") (pinfunction "COM1_VBAT_P$101") (pintype "bidirectional"))
    )
    (net (code "82") (name "unconnected-(U$7-COM1_VBAT-PadP$103)") (class "Default")
      (node (ref "U$7") (pin "P$103") (pinfunction "COM1_VBAT_P$103") (pintype "bidirectional"))
    )
    (net (code "83") (name "unconnected-(U$7-COM2_GND-PadP$98)") (class "Default")
      (node (ref "U$7") (pin "P$98") (pinfunction "COM2_GND_P$98") (pintype "bidirectional"))
    )
    (net (code "84") (name "unconnected-(U$7-COM2_GND-PadP$100)") (class "Default")
      (node (ref "U$7") (pin "P$100") (pinfunction "COM2_GND_P$100") (pintype "bidirectional"))
    )
    (net (code "85") (name "unconnected-(U$7-COM2_VBAT-PadP$97)") (class "Default")
      (node (ref "U$7") (pin "P$97") (pinfunction "COM2_VBAT_P$97") (pintype "bidirectional"))
    )
    (net (code "86") (name "unconnected-(U$7-COM2_VBAT-PadP$99)") (class "Default")
      (node (ref "U$7") (pin "P$99") (pinfunction "COM2_VBAT_P$99") (pintype "bidirectional"))
    )
    (net (code "87") (name "unconnected-(U$7-ESTIMAT_GND-PadP$78)") (class "Default")
      (node (ref "U$7") (pin "P$78") (pinfunction "ESTIMAT_GND_P$78") (pintype "bidirectional"))
    )
    (net (code "88") (name "unconnected-(U$7-ESTIMAT_GND-PadP$80)") (class "Default")
      (node (ref "U$7") (pin "P$80") (pinfunction "ESTIMAT_GND_P$80") (pintype "bidirectional"))
    )
    (net (code "89") (name "unconnected-(U$7-ESTIMAT_I2C_SCL-PadP$70)") (class "Default")
      (node (ref "U$7") (pin "P$70") (pinfunction "ESTIMAT_I2C_SCL_P$70") (pintype "bidirectional"))
    )
    (net (code "90") (name "unconnected-(U$7-ESTIMAT_I2C_SDA-PadP$69)") (class "Default")
      (node (ref "U$7") (pin "P$69") (pinfunction "ESTIMAT_I2C_SDA_P$69") (pintype "bidirectional"))
    )
    (net (code "91") (name "unconnected-(U$7-ESTIMAT_VBAT-PadP$77)") (class "Default")
      (node (ref "U$7") (pin "P$77") (pinfunction "ESTIMAT_VBAT_P$77") (pintype "bidirectional"))
    )
    (net (code "92") (name "unconnected-(U$7-ESTIMAT_VBAT-PadP$79)") (class "Default")
      (node (ref "U$7") (pin "P$79") (pinfunction "ESTIMAT_VBAT_P$79") (pintype "bidirectional"))
    )
    (net (code "93") (name "unconnected-(U$7-MAG1_PWM-PadP$73)") (class "Default")
      (node (ref "U$7") (pin "P$73") (pinfunction "MAG1_PWM_P$73") (pintype "bidirectional"))
    )
    (net (code "94") (name "unconnected-(U$7-MAG2_PWM-PadP$74)") (class "Default")
      (node (ref "U$7") (pin "P$74") (pinfunction "MAG2_PWM_P$74") (pintype "bidirectional"))
    )
    (net (code "95") (name "unconnected-(U$7-MAG3_PWM-PadP$75)") (class "Default")
      (node (ref "U$7") (pin "P$75") (pinfunction "MAG3_PWM_P$75") (pintype "bidirectional"))
    )
    (net (code "96") (name "unconnected-(U$7-MCU_GND-PadP$46)") (class "Default")
      (node (ref "U$7") (pin "P$46") (pinfunction "MCU_GND_P$46") (pintype "bidirectional"))
    )
    (net (code "97") (name "unconnected-(U$7-MCU_GND-PadP$47)") (class "Default")
      (node (ref "U$7") (pin "P$47") (pinfunction "MCU_GND_P$47") (pintype "bidirectional"))
    )
    (net (code "98") (name "unconnected-(U$7-MCU_GND-PadP$58)") (class "Default")
      (node (ref "U$7") (pin "P$58") (pinfunction "MCU_GND_P$58") (pintype "bidirectional"))
    )
    (net (code "99") (name "unconnected-(U$7-MCU_GND-PadP$59)") (class "Default")
      (node (ref "U$7") (pin "P$59") (pinfunction "MCU_GND_P$59") (pintype "bidirectional"))
    )
    (net (code "100") (name "unconnected-(U$7-PPT_GND-PadP$1)") (class "Default")
      (node (ref "U$7") (pin "P$1") (pinfunction "PPT_GND_P$1") (pintype "bidirectional"))
    )
    (net (code "101") (name "unconnected-(U$7-PPT_GND-PadP$3)") (class "Default")
      (node (ref "U$7") (pin "P$3") (pinfunction "PPT_GND_P$3") (pintype "bidirectional"))
    )
    (net (code "102") (name "unconnected-(U$7-PPT_GND-PadP$6)") (class "Default")
      (node (ref "U$7") (pin "P$6") (pinfunction "PPT_GND_P$6") (pintype "bidirectional"))
    )
    (net (code "103") (name "unconnected-(U$7-PPT_GND-PadP$8)") (class "Default")
      (node (ref "U$7") (pin "P$8") (pinfunction "PPT_GND_P$8") (pintype "bidirectional"))
    )
    (net (code "104") (name "unconnected-(U$7-PPT_GND-PadP$9)") (class "Default")
      (node (ref "U$7") (pin "P$9") (pinfunction "PPT_GND_P$9") (pintype "bidirectional"))
    )
    (net (code "105") (name "unconnected-(U$7-PPT_GND-PadP$11)") (class "Default")
      (node (ref "U$7") (pin "P$11") (pinfunction "PPT_GND_P$11") (pintype "bidirectional"))
    )
    (net (code "106") (name "unconnected-(U$7-PPT_GND-PadP$14)") (class "Default")
      (node (ref "U$7") (pin "P$14") (pinfunction "PPT_GND_P$14") (pintype "bidirectional"))
    )
    (net (code "107") (name "unconnected-(U$7-PPT_GND-PadP$16)") (class "Default")
      (node (ref "U$7") (pin "P$16") (pinfunction "PPT_GND_P$16") (pintype "bidirectional"))
    )
    (net (code "108") (name "unconnected-(U$7-PPT_VBAT-PadP$2)") (class "Default")
      (node (ref "U$7") (pin "P$2") (pinfunction "PPT_VBAT_P$2") (pintype "bidirectional"))
    )
    (net (code "109") (name "unconnected-(U$7-PPT_VBAT-PadP$4)") (class "Default")
      (node (ref "U$7") (pin "P$4") (pinfunction "PPT_VBAT_P$4") (pintype "bidirectional"))
    )
    (net (code "110") (name "unconnected-(U$7-PPT_VBAT-PadP$5)") (class "Default")
      (node (ref "U$7") (pin "P$5") (pinfunction "PPT_VBAT_P$5") (pintype "bidirectional"))
    )
    (net (code "111") (name "unconnected-(U$7-PPT_VBAT-PadP$7)") (class "Default")
      (node (ref "U$7") (pin "P$7") (pinfunction "PPT_VBAT_P$7") (pintype "bidirectional"))
    )
    (net (code "112") (name "unconnected-(U$7-PPT_VBAT-PadP$10)") (class "Default")
      (node (ref "U$7") (pin "P$10") (pinfunction "PPT_VBAT_P$10") (pintype "bidirectional"))
    )
    (net (code "113") (name "unconnected-(U$7-PPT_VBAT-PadP$12)") (class "Default")
      (node (ref "U$7") (pin "P$12") (pinfunction "PPT_VBAT_P$12") (pintype "bidirectional"))
    )
    (net (code "114") (name "unconnected-(U$7-PPT_VBAT-PadP$13)") (class "Default")
      (node (ref "U$7") (pin "P$13") (pinfunction "PPT_VBAT_P$13") (pintype "bidirectional"))
    )
    (net (code "115") (name "unconnected-(U$7-PPT_VBAT-PadP$15)") (class "Default")
      (node (ref "U$7") (pin "P$15") (pinfunction "PPT_VBAT_P$15") (pintype "bidirectional"))
    )
    (net (code "116") (name "unconnected-(U$7-PadP$33)") (class "Default")
      (node (ref "U$7") (pin "P$33") (pinfunction "P$33_P$33") (pintype "bidirectional"))
    )
    (net (code "117") (name "unconnected-(U$7-PadP$34)") (class "Default")
      (node (ref "U$7") (pin "P$34") (pinfunction "P$34_P$34") (pintype "bidirectional"))
    )
    (net (code "118") (name "unconnected-(U$7-PadP$35)") (class "Default")
      (node (ref "U$7") (pin "P$35") (pinfunction "P$35_P$35") (pintype "bidirectional"))
    )
    (net (code "119") (name "unconnected-(U$7-PadP$36)") (class "Default")
      (node (ref "U$7") (pin "P$36") (pinfunction "P$36_P$36") (pintype "bidirectional"))
    )
    (net (code "120") (name "unconnected-(U$7-PadP$37)") (class "Default")
      (node (ref "U$7") (pin "P$37") (pinfunction "P$37_P$37") (pintype "bidirectional"))
    )
    (net (code "121") (name "unconnected-(U$7-PadP$38)") (class "Default")
      (node (ref "U$7") (pin "P$38") (pinfunction "P$38_P$38") (pintype "bidirectional"))
    )
    (net (code "122") (name "unconnected-(U$7-PadP$39)") (class "Default")
      (node (ref "U$7") (pin "P$39") (pinfunction "P$39_P$39") (pintype "bidirectional"))
    )
    (net (code "123") (name "unconnected-(U$7-PadP$40)") (class "Default")
      (node (ref "U$7") (pin "P$40") (pinfunction "P$40_P$40") (pintype "bidirectional"))
    )
    (net (code "124") (name "unconnected-(U$7-PadP$41)") (class "Default")
      (node (ref "U$7") (pin "P$41") (pinfunction "P$41_P$41") (pintype "bidirectional"))
    )
    (net (code "125") (name "unconnected-(U$7-PadP$42)") (class "Default")
      (node (ref "U$7") (pin "P$42") (pinfunction "P$42_P$42") (pintype "bidirectional"))
    )
    (net (code "126") (name "unconnected-(U$7-PadP$43)") (class "Default")
      (node (ref "U$7") (pin "P$43") (pinfunction "P$43_P$43") (pintype "bidirectional"))
    )
    (net (code "127") (name "unconnected-(U$7-PadP$44)") (class "Default")
      (node (ref "U$7") (pin "P$44") (pinfunction "P$44_P$44") (pintype "bidirectional"))
    )
    (net (code "128") (name "unconnected-(U$7-PadP$48)") (class "Default")
      (node (ref "U$7") (pin "P$48") (pinfunction "P$48_P$48") (pintype "bidirectional"))
    )
    (net (code "129") (name "unconnected-(U$7-PadP$52)") (class "Default")
      (node (ref "U$7") (pin "P$52") (pinfunction "P$52_P$52") (pintype "bidirectional"))
    )
    (net (code "130") (name "unconnected-(U$7-PadP$56)") (class "Default")
      (node (ref "U$7") (pin "P$56") (pinfunction "P$56_P$56") (pintype "bidirectional"))
    )
    (net (code "131") (name "unconnected-(U$7-PadP$60)") (class "Default")
      (node (ref "U$7") (pin "P$60") (pinfunction "P$60_P$60") (pintype "bidirectional"))
    )
    (net (code "132") (name "unconnected-(U$7-PadP$61)") (class "Default")
      (node (ref "U$7") (pin "P$61") (pinfunction "P$61_P$61") (pintype "bidirectional"))
    )
    (net (code "133") (name "unconnected-(U$7-PadP$62)") (class "Default")
      (node (ref "U$7") (pin "P$62") (pinfunction "P$62_P$62") (pintype "bidirectional"))
    )
    (net (code "134") (name "unconnected-(U$7-PadP$63)") (class "Default")
      (node (ref "U$7") (pin "P$63") (pinfunction "P$63_P$63") (pintype "bidirectional"))
    )
    (net (code "135") (name "unconnected-(U$7-PadP$64)") (class "Default")
      (node (ref "U$7") (pin "P$64") (pinfunction "P$64_P$64") (pintype "bidirectional"))
    )
    (net (code "136") (name "unconnected-(U$7-PadP$65)") (class "Default")
      (node (ref "U$7") (pin "P$65") (pinfunction "P$65_P$65") (pintype "bidirectional"))
    )
    (net (code "137") (name "unconnected-(U$7-PadP$66)") (class "Default")
      (node (ref "U$7") (pin "P$66") (pinfunction "P$66_P$66") (pintype "bidirectional"))
    )
    (net (code "138") (name "unconnected-(U$7-PadP$67)") (class "Default")
      (node (ref "U$7") (pin "P$67") (pinfunction "P$67_P$67") (pintype "bidirectional"))
    )
    (net (code "139") (name "unconnected-(U$7-PadP$68)") (class "Default")
      (node (ref "U$7") (pin "P$68") (pinfunction "P$68_P$68") (pintype "bidirectional"))
    )
    (net (code "140") (name "unconnected-(U$7-PadP$71)") (class "Default")
      (node (ref "U$7") (pin "P$71") (pinfunction "P$71_P$71") (pintype "bidirectional"))
    )
    (net (code "141") (name "unconnected-(U$7-PadP$72)") (class "Default")
      (node (ref "U$7") (pin "P$72") (pinfunction "P$72_P$72") (pintype "bidirectional"))
    )
    (net (code "142") (name "unconnected-(U$7-PadP$76)") (class "Default")
      (node (ref "U$7") (pin "P$76") (pinfunction "P$76_P$76") (pintype "bidirectional"))
    )
    (net (code "143") (name "unconnected-(U$7-PadP$91)") (class "Default")
      (node (ref "U$7") (pin "P$91") (pinfunction "P$91_P$91") (pintype "bidirectional"))
    )
    (net (code "144") (name "unconnected-(U$7-PadP$92)") (class "Default")
      (node (ref "U$7") (pin "P$92") (pinfunction "P$92_P$92") (pintype "bidirectional"))
    )
    (net (code "145") (name "unconnected-(U$7-PadP$95)") (class "Default")
      (node (ref "U$7") (pin "P$95") (pinfunction "P$95_P$95") (pintype "bidirectional"))
    )
    (net (code "146") (name "unconnected-(U$7-PadP$96)") (class "Default")
      (node (ref "U$7") (pin "P$96") (pinfunction "P$96_P$96") (pintype "bidirectional"))
    )
    (net (code "147") (name "unconnected-(U$7-RAHS_GND-PadP$94)") (class "Default")
      (node (ref "U$7") (pin "P$94") (pinfunction "RAHS_GND_P$94") (pintype "bidirectional"))
    )
    (net (code "148") (name "unconnected-(U$7-RAHS_VBAT-PadP$93)") (class "Default")
      (node (ref "U$7") (pin "P$93") (pinfunction "RAHS_VBAT_P$93") (pintype "bidirectional"))
    )
  )
)
